# 32U4_Breakout.net
KiCad netlist of a schematic drawn in EAGLE
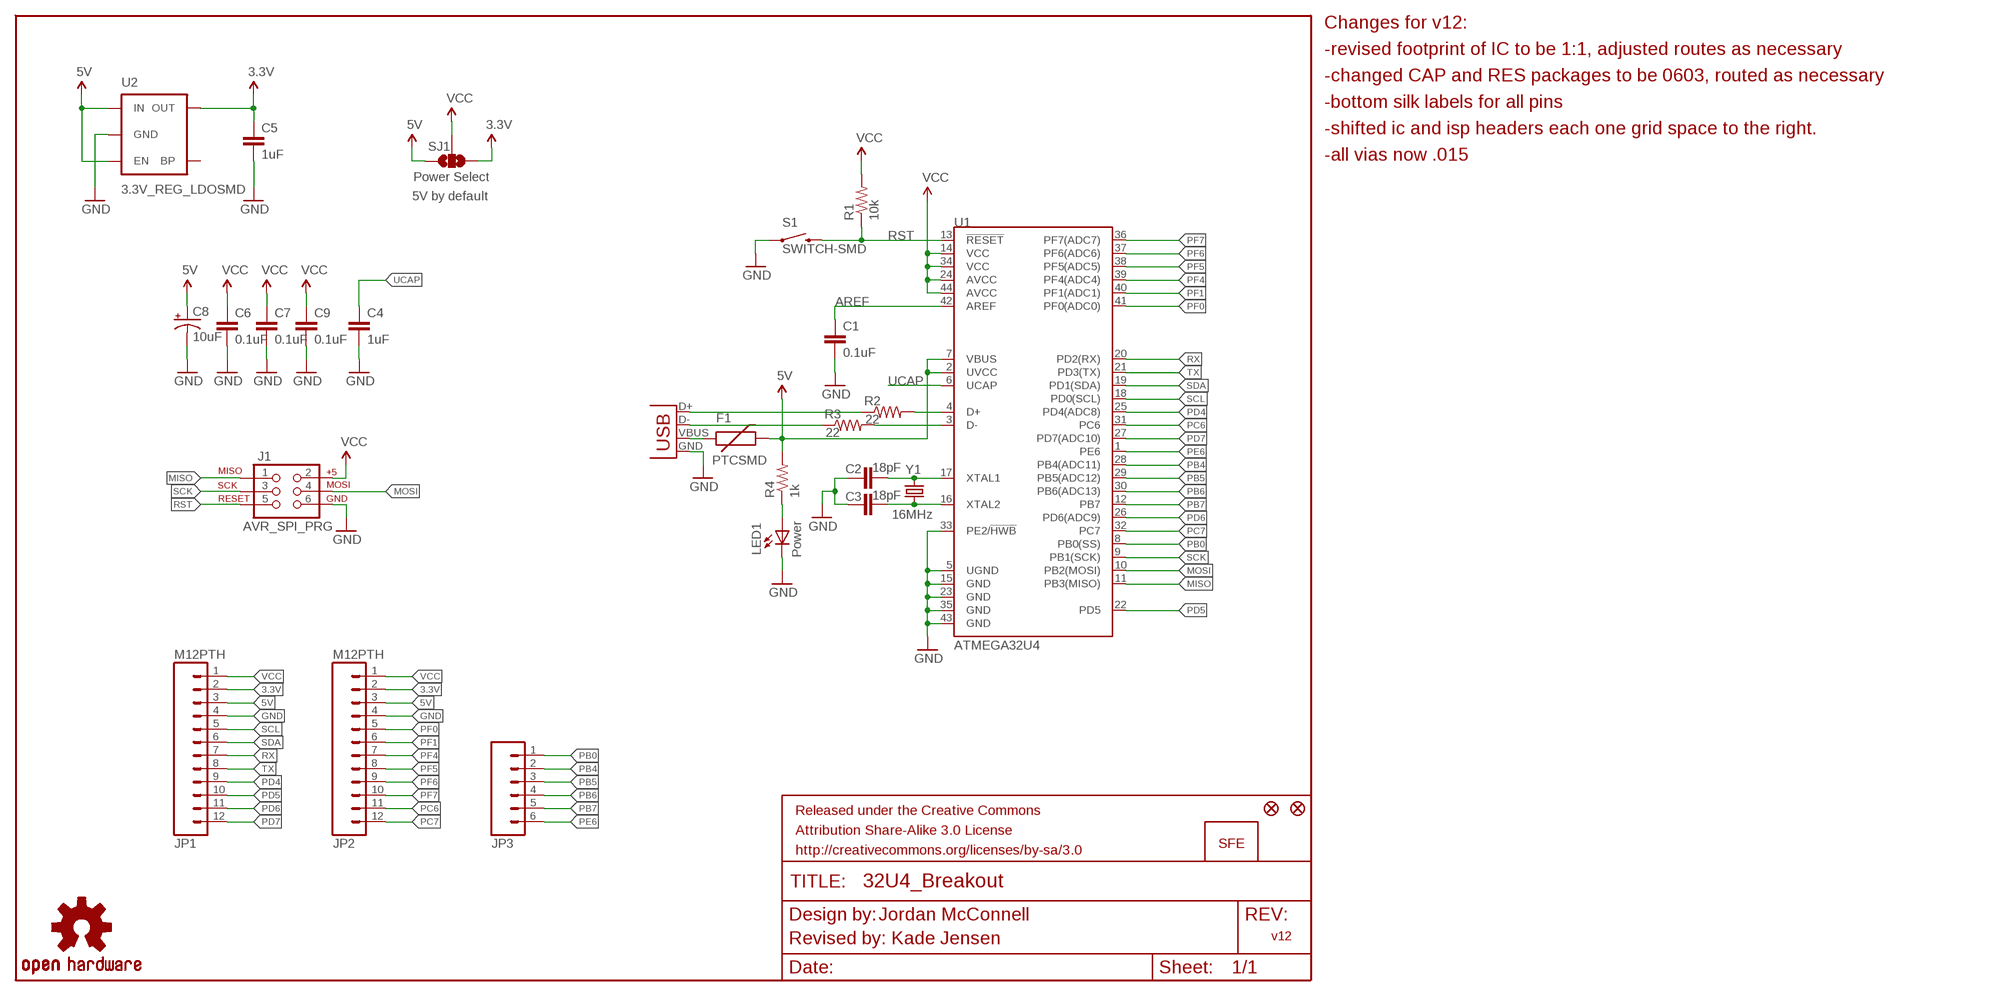
[diagram p0: schematic, sheet 1]

(export (version "E")
  (design (tool "Eeschema 10.0.6"))
  (components
    (comp (ref "C1")
      (value "0.1uF")
      (footprint "eagle-import:0603-CAP")
      (libsource (lib "eagle-import") (part "CAP0603-CAP"))
    )
    (comp (ref "C2")
      (value "18pF")
      (footprint "eagle-import:0603-CAP")
      (libsource (lib "eagle-import") (part "CAP0603-CAP"))
    )
    (comp (ref "C3")
      (value "18pF")
      (footprint "eagle-import:0603-CAP")
      (libsource (lib "eagle-import") (part "CAP0603-CAP"))
    )
    (comp (ref "C4")
      (value "1uF")
      (footprint "eagle-import:0603-CAP")
      (libsource (lib "eagle-import") (part "CAP0603-CAP"))
    )
    (comp (ref "C5")
      (value "1uF")
      (footprint "eagle-import:0603-CAP")
      (libsource (lib "eagle-import") (part "CAP0603-CAP"))
    )
    (comp (ref "C6")
      (value "0.1uF")
      (footprint "eagle-import:0603-CAP")
      (libsource (lib "eagle-import") (part "CAP0603-CAP"))
    )
    (comp (ref "C7")
      (value "0.1uF")
      (footprint "eagle-import:0603-CAP")
      (libsource (lib "eagle-import") (part "CAP0603-CAP"))
    )
    (comp (ref "C8")
      (value "10uF")
      (footprint "eagle-import:EIA3216")
      (libsource (lib "eagle-import") (part "CAP_POL1206"))
    )
    (comp (ref "C9")
      (value "0.1uF")
      (footprint "eagle-import:0603-CAP")
      (libsource (lib "eagle-import") (part "CAP0603-CAP"))
    )
    (comp (ref "F1")
      (value "PTCSMD")
      (footprint "eagle-import:PTC-1206")
      (libsource (lib "eagle-import") (part "PTCSMD"))
    )
    (comp (ref "J1")
      (value "AVR_SPI_PRG")
      (footprint "eagle-import:2X3")
      (libsource (lib "eagle-import") (part "AVR_SPI_PRG_6PTH"))
    )
    (comp (ref "JP1")
      (value "M12PTH")
      (footprint "eagle-import:1X12")
      (libsource (lib "eagle-import") (part "M12PTH"))
    )
    (comp (ref "JP2")
      (value "M12PTH")
      (footprint "eagle-import:1X12")
      (libsource (lib "eagle-import") (part "M12PTH"))
    )
    (comp (ref "JP3")
      (value "M06SIP")
      (footprint "eagle-import:1X06")
      (libsource (lib "eagle-import") (part "M06SIP"))
    )
    (comp (ref "JP6")
      (value "FIDUCIAL1X2")
      (footprint "eagle-import:FIDUCIAL-1X2")
      (libsource (lib "eagle-import") (part "FIDUCIAL1X2"))
    )
    (comp (ref "JP7")
      (value "FIDUCIAL1X2")
      (footprint "eagle-import:FIDUCIAL-1X2")
      (libsource (lib "eagle-import") (part "FIDUCIAL1X2"))
    )
    (comp (ref "JP8")
      (value "LOGO-SFENEW")
      (footprint "eagle-import:SFE-NEW-WEBLOGO")
      (libsource (lib "eagle-import") (part "LOGO-SFENEW"))
    )
    (comp (ref "LED1")
      (value "Power")
      (footprint "eagle-import:LED-0603")
      (libsource (lib "eagle-import") (part "LED0603"))
    )
    (comp (ref "R1")
      (value "10k")
      (footprint "eagle-import:0603-RES")
      (libsource (lib "eagle-import") (part "RESISTOR0603-RES"))
    )
    (comp (ref "R2")
      (value "22")
      (footprint "eagle-import:0603-RES")
      (libsource (lib "eagle-import") (part "RESISTOR0603-RES"))
    )
    (comp (ref "R3")
      (value "22")
      (footprint "eagle-import:0603-RES")
      (libsource (lib "eagle-import") (part "RESISTOR0603-RES"))
    )
    (comp (ref "R4")
      (value "1k")
      (footprint "eagle-import:0603-RES")
      (libsource (lib "eagle-import") (part "RESISTOR0603-RES"))
    )
    (comp (ref "S1")
      (value "SWITCH-SMD")
      (footprint "eagle-import:TACTILE_SWITCH_SMD")
      (libsource (lib "eagle-import") (part "SWITCH-MOMENTARY-2SMD"))
    )
    (comp (ref "SJ1")
      (value "Power Select")
      (footprint "eagle-import:SJ_3_PASTE2&3")
      (libsource (lib "eagle-import") (part "SOLDERJUMPER_2WAYPASTE2&3"))
    )
    (comp (ref "U$6")
      (value "OSHW-LOGOM")
      (footprint "eagle-import:OSHW-LOGO-M")
      (libsource (lib "eagle-import") (part "OSHW-LOGOM"))
    )
    (comp (ref "U1")
      (value "ATMEGA32U4")
      (footprint "eagle-import:QFN-44-NOPAD_1_1")
      (libsource (lib "eagle-import") (part "ATMEGA32U41{colon}1"))
    )
    (comp (ref "U2")
      (value "3.3V_REG_LDOSMD")
      (footprint "eagle-import:SOT23-5")
      (libsource (lib "eagle-import") (part "V_REG_LDOSMD"))
    )
    (comp (ref "X1")
      (value "USBSMD")
      (footprint "eagle-import:USB-MINIB")
      (libsource (lib "eagle-import") (part "USBSMD"))
    )
    (comp (ref "Y1")
      (value "16MHz")
      (footprint "eagle-import:CRYSTAL-SMD-5X3")
      (libsource (lib "eagle-import") (part "CRYSTAL5X3"))
    )
  )
  (nets
    (net (code "1") (name "/AREF") (class "Default")
      (node (ref "C1") (pin "1") (pinfunction "1_1") (pintype "passive"))
      (node (ref "U1") (pin "42") (pinfunction "AREF_42") (pintype "bidirectional"))
    )
    (net (code "2") (name "3.3V") (class "Default")
      (node (ref "C5") (pin "1") (pinfunction "1_1") (pintype "passive"))
      (node (ref "JP1") (pin "2") (pinfunction "2_2") (pintype "passive"))
      (node (ref "JP2") (pin "2") (pinfunction "2_2") (pintype "passive"))
      (node (ref "SJ1") (pin "1") (pinfunction "1_1") (pintype "passive"))
      (node (ref "U2") (pin "5") (pinfunction "OUT_5") (pintype "passive"))
    )
    (net (code "3") (name "5V") (class "Default")
      (node (ref "C8") (pin "A") (pinfunction "+_A") (pintype "passive"))
      (node (ref "F1") (pin "2") (pinfunction "2_2") (pintype "bidirectional"))
      (node (ref "JP1") (pin "3") (pinfunction "3_3") (pintype "passive"))
      (node (ref "JP2") (pin "3") (pinfunction "3_3") (pintype "passive"))
      (node (ref "R4") (pin "2") (pinfunction "2_2") (pintype "passive"))
      (node (ref "SJ1") (pin "3") (pinfunction "3_3") (pintype "passive"))
      (node (ref "U1") (pin "2") (pinfunction "UVCC_2") (pintype "bidirectional"))
      (node (ref "U1") (pin "7") (pinfunction "VBUS_7") (pintype "bidirectional"))
      (node (ref "U2") (pin "1") (pinfunction "IN_1") (pintype "input"))
      (node (ref "U2") (pin "3") (pinfunction "EN_3") (pintype "input"))
    )
    (net (code "4") (name "GND") (class "Default")
      (node (ref "C1") (pin "2") (pinfunction "2_2") (pintype "passive"))
      (node (ref "C2") (pin "1") (pinfunction "1_1") (pintype "passive"))
      (node (ref "C3") (pin "1") (pinfunction "1_1") (pintype "passive"))
      (node (ref "C4") (pin "2") (pinfunction "2_2") (pintype "passive"))
      (node (ref "C5") (pin "2") (pinfunction "2_2") (pintype "passive"))
      (node (ref "C6") (pin "2") (pinfunction "2_2") (pintype "passive"))
      (node (ref "C7") (pin "2") (pinfunction "2_2") (pintype "passive"))
      (node (ref "C8") (pin "C") (pinfunction "-_C") (pintype "passive"))
      (node (ref "C9") (pin "2") (pinfunction "2_2") (pintype "passive"))
      (node (ref "J1") (pin "6") (pinfunction "6_6") (pintype "passive"))
      (node (ref "JP1") (pin "4") (pinfunction "4_4") (pintype "passive"))
      (node (ref "JP2") (pin "4") (pinfunction "4_4") (pintype "passive"))
      (node (ref "LED1") (pin "C") (pinfunction "C_C") (pintype "passive"))
      (node (ref "S1") (pin "1") (pinfunction "1_1") (pintype "passive"))
      (node (ref "U1") (pin "15") (pinfunction "GND_15") (pintype "bidirectional"))
      (node (ref "U1") (pin "23") (pinfunction "GND_23") (pintype "bidirectional"))
      (node (ref "U1") (pin "33") (pinfunction "PE2/~{HWB}_33") (pintype "bidirectional"))
      (node (ref "U1") (pin "35") (pinfunction "GND_35") (pintype "bidirectional"))
      (node (ref "U1") (pin "43") (pinfunction "GND_43") (pintype "bidirectional"))
      (node (ref "U1") (pin "5") (pinfunction "UGND_5") (pintype "bidirectional"))
      (node (ref "U2") (pin "2") (pinfunction "GND_2") (pintype "input"))
      (node (ref "X1") (pin "GND") (pinfunction "GND_GND") (pintype "bidirectional"))
    )
    (net (code "5") (name "MISO") (class "Default")
      (node (ref "J1") (pin "1") (pinfunction "1_1") (pintype "passive"))
      (node (ref "U1") (pin "11") (pinfunction "PB3(MISO)_11") (pintype "bidirectional"))
    )
    (net (code "6") (name "MOSI") (class "Default")
      (node (ref "J1") (pin "4") (pinfunction "4_4") (pintype "passive"))
      (node (ref "U1") (pin "10") (pinfunction "PB2(MOSI)_10") (pintype "bidirectional"))
    )
    (net (code "7") (name "Net-(F1-Pad1)") (class "Default")
      (node (ref "F1") (pin "1") (pinfunction "1_1") (pintype "bidirectional"))
      (node (ref "X1") (pin "VBUS") (pinfunction "VBUS_VBUS") (pintype "bidirectional"))
    )
    (net (code "8") (name "Net-(LED1-PadA)") (class "Default")
      (node (ref "LED1") (pin "A") (pinfunction "A_A") (pintype "passive"))
      (node (ref "R4") (pin "1") (pinfunction "1_1") (pintype "passive"))
    )
    (net (code "9") (name "Net-(R2-Pad1)") (class "Default")
      (node (ref "R2") (pin "1") (pinfunction "1_1") (pintype "passive"))
      (node (ref "X1") (pin "D+") (pinfunction "D+_D+") (pintype "bidirectional"))
    )
    (net (code "10") (name "Net-(R3-Pad1)") (class "Default")
      (node (ref "R3") (pin "1") (pinfunction "1_1") (pintype "passive"))
      (node (ref "X1") (pin "D-") (pinfunction "D-_D-") (pintype "bidirectional"))
    )
    (net (code "11") (name "Net-(U1-D+)") (class "Default")
      (node (ref "R2") (pin "2") (pinfunction "2_2") (pintype "passive"))
      (node (ref "U1") (pin "4") (pinfunction "D+_4") (pintype "bidirectional"))
    )
    (net (code "12") (name "Net-(U1-D-)") (class "Default")
      (node (ref "R3") (pin "2") (pinfunction "2_2") (pintype "passive"))
      (node (ref "U1") (pin "3") (pinfunction "D-_3") (pintype "bidirectional"))
    )
    (net (code "13") (name "Net-(U1-XTAL1)") (class "Default")
      (node (ref "C2") (pin "2") (pinfunction "2_2") (pintype "passive"))
      (node (ref "U1") (pin "17") (pinfunction "XTAL1_17") (pintype "bidirectional"))
      (node (ref "Y1") (pin "3") (pinfunction "2_3") (pintype "passive"))
    )
    (net (code "14") (name "Net-(U1-XTAL2)") (class "Default")
      (node (ref "C3") (pin "2") (pinfunction "2_2") (pintype "passive"))
      (node (ref "U1") (pin "16") (pinfunction "XTAL2_16") (pintype "bidirectional"))
      (node (ref "Y1") (pin "1") (pinfunction "1_1") (pintype "passive"))
    )
    (net (code "15") (name "PB0") (class "Default")
      (node (ref "JP3") (pin "1") (pinfunction "1_1") (pintype "passive"))
      (node (ref "U1") (pin "8") (pinfunction "PB0(SS)_8") (pintype "bidirectional"))
    )
    (net (code "16") (name "PB4") (class "Default")
      (node (ref "JP3") (pin "2") (pinfunction "2_2") (pintype "passive"))
      (node (ref "U1") (pin "28") (pinfunction "PB4(ADC11)_28") (pintype "bidirectional"))
    )
    (net (code "17") (name "PB5") (class "Default")
      (node (ref "JP3") (pin "3") (pinfunction "3_3") (pintype "passive"))
      (node (ref "U1") (pin "29") (pinfunction "PB5(ADC12)_29") (pintype "bidirectional"))
    )
    (net (code "18") (name "PB6") (class "Default")
      (node (ref "JP3") (pin "4") (pinfunction "4_4") (pintype "passive"))
      (node (ref "U1") (pin "30") (pinfunction "PB6(ADC13)_30") (pintype "bidirectional"))
    )
    (net (code "19") (name "PB7") (class "Default")
      (node (ref "JP3") (pin "5") (pinfunction "5_5") (pintype "passive"))
      (node (ref "U1") (pin "12") (pinfunction "PB7_12") (pintype "bidirectional"))
    )
    (net (code "20") (name "PC6") (class "Default")
      (node (ref "JP2") (pin "11") (pinfunction "11_11") (pintype "passive"))
      (node (ref "U1") (pin "31") (pinfunction "PC6_31") (pintype "bidirectional"))
    )
    (net (code "21") (name "PC7") (class "Default")
      (node (ref "JP2") (pin "12") (pinfunction "12_12") (pintype "passive"))
      (node (ref "U1") (pin "32") (pinfunction "PC7_32") (pintype "bidirectional"))
    )
    (net (code "22") (name "PD4") (class "Default")
      (node (ref "JP1") (pin "9") (pinfunction "9_9") (pintype "passive"))
      (node (ref "U1") (pin "25") (pinfunction "PD4(ADC8)_25") (pintype "bidirectional"))
    )
    (net (code "23") (name "PD5") (class "Default")
      (node (ref "JP1") (pin "10") (pinfunction "10_10") (pintype "passive"))
      (node (ref "U1") (pin "22") (pinfunction "PD5_22") (pintype "bidirectional"))
    )
    (net (code "24") (name "PD6") (class "Default")
      (node (ref "JP1") (pin "11") (pinfunction "11_11") (pintype "passive"))
      (node (ref "U1") (pin "26") (pinfunction "PD6(ADC9)_26") (pintype "bidirectional"))
    )
    (net (code "25") (name "PD7") (class "Default")
      (node (ref "JP1") (pin "12") (pinfunction "12_12") (pintype "passive"))
      (node (ref "U1") (pin "27") (pinfunction "PD7(ADC10)_27") (pintype "bidirectional"))
    )
    (net (code "26") (name "PE6") (class "Default")
      (node (ref "JP3") (pin "6") (pinfunction "6_6") (pintype "passive"))
      (node (ref "U1") (pin "1") (pinfunction "PE6_1") (pintype "bidirectional"))
    )
    (net (code "27") (name "PF0") (class "Default")
      (node (ref "JP2") (pin "5") (pinfunction "5_5") (pintype "passive"))
      (node (ref "U1") (pin "41") (pinfunction "PF0(ADC0)_41") (pintype "bidirectional"))
    )
    (net (code "28") (name "PF1") (class "Default")
      (node (ref "JP2") (pin "6") (pinfunction "6_6") (pintype "passive"))
      (node (ref "U1") (pin "40") (pinfunction "PF1(ADC1)_40") (pintype "bidirectional"))
    )
    (net (code "29") (name "PF4") (class "Default")
      (node (ref "JP2") (pin "7") (pinfunction "7_7") (pintype "passive"))
      (node (ref "U1") (pin "39") (pinfunction "PF4(ADC4)_39") (pintype "bidirectional"))
    )
    (net (code "30") (name "PF5") (class "Default")
      (node (ref "JP2") (pin "8") (pinfunction "8_8") (pintype "passive"))
      (node (ref "U1") (pin "38") (pinfunction "PF5(ADC5)_38") (pintype "bidirectional"))
    )
    (net (code "31") (name "PF6") (class "Default")
      (node (ref "JP2") (pin "9") (pinfunction "9_9") (pintype "passive"))
      (node (ref "U1") (pin "37") (pinfunction "PF6(ADC6)_37") (pintype "bidirectional"))
    )
    (net (code "32") (name "PF7") (class "Default")
      (node (ref "JP2") (pin "10") (pinfunction "10_10") (pintype "passive"))
      (node (ref "U1") (pin "36") (pinfunction "PF7(ADC7)_36") (pintype "bidirectional"))
    )
    (net (code "33") (name "RST") (class "Default")
      (node (ref "J1") (pin "5") (pinfunction "5_5") (pintype "passive"))
      (node (ref "R1") (pin "1") (pinfunction "1_1") (pintype "passive"))
      (node (ref "S1") (pin "3") (pinfunction "2_3") (pintype "passive"))
      (node (ref "U1") (pin "13") (pinfunction "~{RESET}_13") (pintype "bidirectional"))
    )
    (net (code "34") (name "RX") (class "Default")
      (node (ref "JP1") (pin "7") (pinfunction "7_7") (pintype "passive"))
      (node (ref "U1") (pin "20") (pinfunction "PD2(RX)_20") (pintype "bidirectional"))
    )
    (net (code "35") (name "SCK") (class "Default")
      (node (ref "J1") (pin "3") (pinfunction "3_3") (pintype "passive"))
      (node (ref "U1") (pin "9") (pinfunction "PB1(SCK)_9") (pintype "bidirectional"))
    )
    (net (code "36") (name "SCL") (class "Default")
      (node (ref "JP1") (pin "5") (pinfunction "5_5") (pintype "passive"))
      (node (ref "U1") (pin "18") (pinfunction "PD0(SCL)_18") (pintype "bidirectional"))
    )
    (net (code "37") (name "SDA") (class "Default")
      (node (ref "JP1") (pin "6") (pinfunction "6_6") (pintype "passive"))
      (node (ref "U1") (pin "19") (pinfunction "PD1(SDA)_19") (pintype "bidirectional"))
    )
    (net (code "38") (name "TX") (class "Default")
      (node (ref "JP1") (pin "8") (pinfunction "8_8") (pintype "passive"))
      (node (ref "U1") (pin "21") (pinfunction "PD3(TX)_21") (pintype "bidirectional"))
    )
    (net (code "39") (name "UCAP") (class "Default")
      (node (ref "C4") (pin "1") (pinfunction "1_1") (pintype "passive"))
      (node (ref "U1") (pin "6") (pinfunction "UCAP_6") (pintype "bidirectional"))
    )
    (net (code "40") (name "VCC") (class "Default")
      (node (ref "C6") (pin "1") (pinfunction "1_1") (pintype "passive"))
      (node (ref "C7") (pin "1") (pinfunction "1_1") (pintype "passive"))
      (node (ref "C9") (pin "1") (pinfunction "1_1") (pintype "passive"))
      (node (ref "J1") (pin "2") (pinfunction "2_2") (pintype "passive"))
      (node (ref "JP1") (pin "1") (pinfunction "1_1") (pintype "passive"))
      (node (ref "JP2") (pin "1") (pinfunction "1_1") (pintype "passive"))
      (node (ref "R1") (pin "2") (pinfunction "2_2") (pintype "passive"))
      (node (ref "SJ1") (pin "2") (pinfunction "2_2") (pintype "passive"))
      (node (ref "U1") (pin "14") (pinfunction "VCC_14") (pintype "bidirectional"))
      (node (ref "U1") (pin "24") (pinfunction "AVCC_24") (pintype "bidirectional"))
      (node (ref "U1") (pin "34") (pinfunction "VCC_34") (pintype "bidirectional"))
      (node (ref "U1") (pin "44") (pinfunction "AVCC_44") (pintype "bidirectional"))
    )
    (net (code "41") (name "unconnected-(U2-BP-Pad4)") (class "Default")
      (node (ref "U2") (pin "4") (pinfunction "BP_4") (pintype "input"))
    )
  )
)
